# QUTMS-BrakeLight-S02-V01.net
KiCad netlist of a schematic drawn in Altium Designer
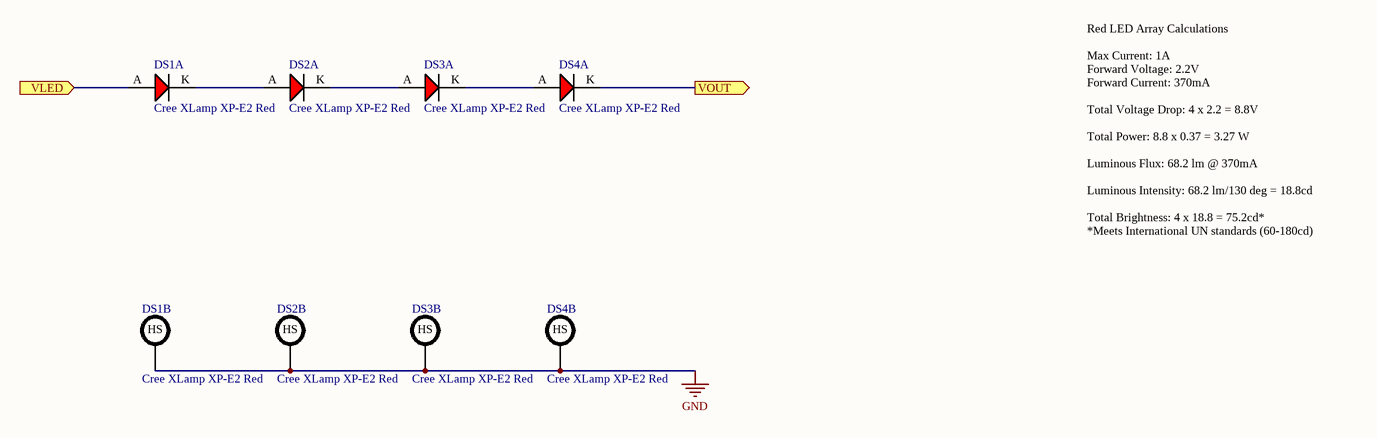
[diagram p0: QUTMS-BrakeLight-S02-V01.SchDoc]

(export (version "E")
  (design (tool "Eeschema 10.0.6"))
  (components
    (comp (ref "DS1")
      (value "Cree XLamp XP-E2 Red")
      (footprint "Cree XLamp XP-E2")
      (description "XPEBRD-L1-0000-00601 -  High Brightness LED, XLamp XP-E2 Series, Red, 630 nm, 130 °, 62 lm, 1 A")
      (libsource (lib "QUTMS_LEDLibrary") (part "Cree XLamp XP-E2 Red"))
    )
    (comp (ref "DS2")
      (value "Cree XLamp XP-E2 Red")
      (footprint "Cree XLamp XP-E2")
      (description "XPEBRD-L1-0000-00601 -  High Brightness LED, XLamp XP-E2 Series, Red, 630 nm, 130 °, 62 lm, 1 A")
      (libsource (lib "QUTMS_LEDLibrary") (part "Cree XLamp XP-E2 Red"))
    )
    (comp (ref "DS3")
      (value "Cree XLamp XP-E2 Red")
      (footprint "Cree XLamp XP-E2")
      (description "XPEBRD-L1-0000-00601 -  High Brightness LED, XLamp XP-E2 Series, Red, 630 nm, 130 °, 62 lm, 1 A")
      (libsource (lib "QUTMS_LEDLibrary") (part "Cree XLamp XP-E2 Red"))
    )
    (comp (ref "DS4")
      (value "Cree XLamp XP-E2 Red")
      (footprint "Cree XLamp XP-E2")
      (description "XPEBRD-L1-0000-00601 -  High Brightness LED, XLamp XP-E2 Series, Red, 630 nm, 130 °, 62 lm, 1 A")
      (libsource (lib "QUTMS_LEDLibrary") (part "Cree XLamp XP-E2 Red"))
    )
  )
  (nets
    (net (code "1") (name "/VLED") (class "Default")
      (node (ref "DS1") (pin "A") (pinfunction "A_A") (pintype "passive"))
    )
    (net (code "2") (name "/VOUT") (class "Default")
      (node (ref "DS4") (pin "K") (pinfunction "K_K") (pintype "passive"))
    )
    (net (code "3") (name "GND") (class "Default")
      (node (ref "DS1") (pin "HS") (pinfunction "HS_HS") (pintype "passive"))
      (node (ref "DS2") (pin "HS") (pinfunction "HS_HS") (pintype "passive"))
      (node (ref "DS3") (pin "HS") (pinfunction "HS_HS") (pintype "passive"))
      (node (ref "DS4") (pin "HS") (pinfunction "HS_HS") (pintype "passive"))
    )
    (net (code "4") (name "Net-(DS1-PadK)") (class "Default")
      (node (ref "DS1") (pin "K") (pinfunction "K_K") (pintype "passive"))
      (node (ref "DS2") (pin "A") (pinfunction "A_A") (pintype "passive"))
    )
    (net (code "5") (name "Net-(DS2-PadK)") (class "Default")
      (node (ref "DS2") (pin "K") (pinfunction "K_K") (pintype "passive"))
      (node (ref "DS3") (pin "A") (pinfunction "A_A") (pintype "passive"))
    )
    (net (code "6") (name "Net-(DS3-PadK)") (class "Default")
      (node (ref "DS3") (pin "K") (pinfunction "K_K") (pintype "passive"))
      (node (ref "DS4") (pin "A") (pinfunction "A_A") (pintype "passive"))
    )
  )
)
